# tie-il34-sdram.net
KiCad netlist of a schematic drawn in Altium Designer
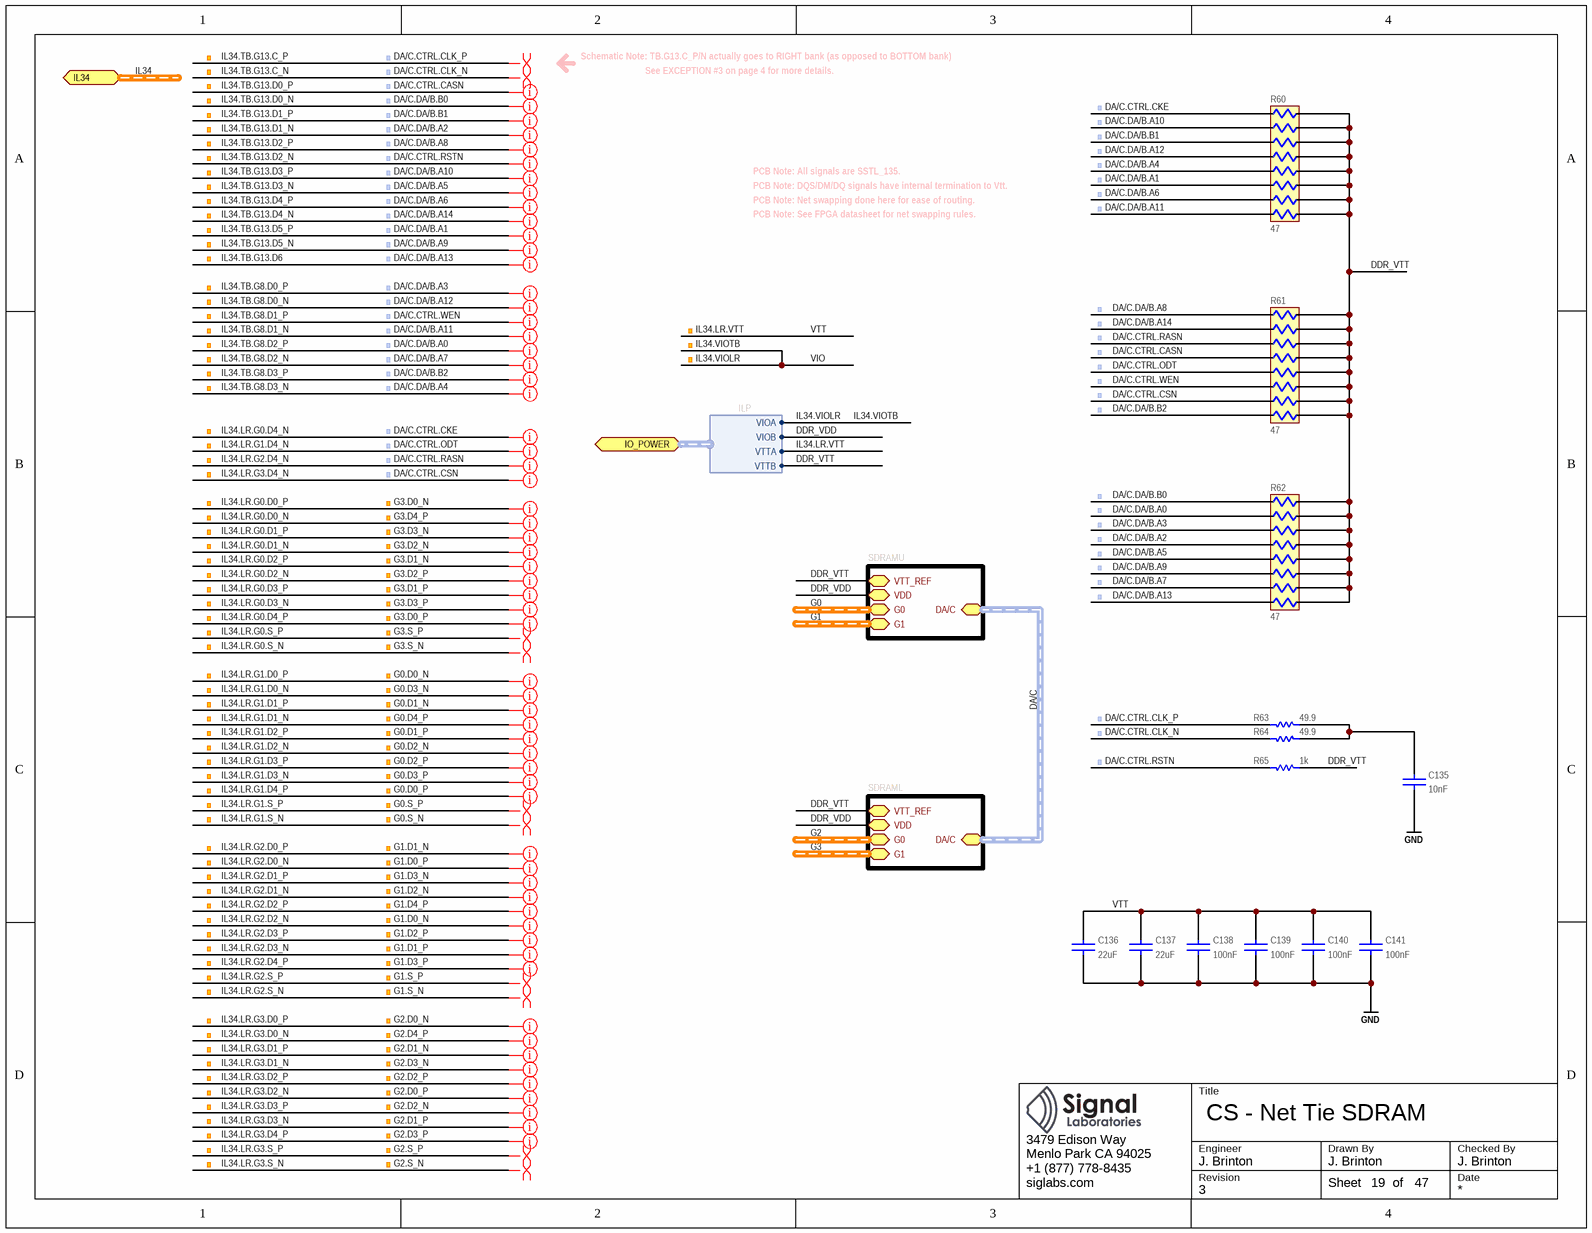
[diagram p0: tie-il34-sdram.SchDoc]

(export (version "E")
  (design (tool "Eeschema 10.0.6"))
  (components
    (comp (ref "C135")
      (value "10nF")
      (footprint "CAPC100X50X55L25N")
      (description "Ceramic Capacitor 10nF ±10% 50V X7R 0402")
      (fields (field (name "VOLTAGE") "50V") (field (name "MANUFACTURER") "Murata"))
      (libsource (lib "generic") (part "CAP"))
    )
    (comp (ref "C136")
      (value "22uF")
      (footprint "CAPC200X125X145L45N")
      (description "Ceramic Capacitor 22uF ±20% 10V X7S 0805")
      (fields (field (name "MANUFACTURER") "TDK") (field (name "TOLERANCE") "±20%"))
      (libsource (lib "generic") (part "CAP"))
    )
    (comp (ref "C137")
      (value "22uF")
      (footprint "CAPC200X125X145L45N")
      (description "Ceramic Capacitor 22uF ±20% 10V X7S 0805")
      (fields (field (name "MANUFACTURER") "TDK") (field (name "TOLERANCE") "±20%"))
      (libsource (lib "generic") (part "CAP"))
    )
    (comp (ref "C138")
      (value "100nF")
      (footprint "CAPC100X50X55L25N")
      (description "Ceramic Capacitor 100nF ±10% 50V X7R 0402")
      (fields (field (name "MANUFACTURER") "Murata") (field (name "TOLERANCE") "±10%"))
      (libsource (lib "generic") (part "CAP"))
    )
    (comp (ref "C139")
      (value "100nF")
      (footprint "CAPC100X50X55L25N")
      (description "Ceramic Capacitor 100nF ±10% 50V X7R 0402")
      (fields (field (name "MANUFACTURER") "Murata") (field (name "TOLERANCE") "±10%"))
      (libsource (lib "generic") (part "CAP"))
    )
    (comp (ref "C140")
      (value "100nF")
      (footprint "CAPC100X50X55L25N")
      (description "Ceramic Capacitor 100nF ±10% 50V X7R 0402")
      (fields (field (name "MANUFACTURER") "Murata") (field (name "TOLERANCE") "±10%"))
      (libsource (lib "generic") (part "CAP"))
    )
    (comp (ref "C141")
      (value "100nF")
      (footprint "CAPC100X50X55L25N")
      (description "Ceramic Capacitor 100nF ±10% 50V X7R 0402")
      (fields (field (name "MANUFACTURER") "Murata") (field (name "TOLERANCE") "±10%"))
      (libsource (lib "generic") (part "CAP"))
    )
    (comp (ref "R60")
      (value "47")
      (footprint "RESCAXE16P50_380X160X55L30X35N")
      (description "8 Resistor Array 47 ±5% 0.0625W 25V 1506")
      (fields (field (name "MANUFACTURER") "Panasonic") (field (name "TOLERANCE") "±5%"))
      (libsource (lib "altium-import") (part "root_0_EXB-2HV470JV_"))
    )
    (comp (ref "R61")
      (value "47")
      (footprint "RESCAXE16P50_380X160X55L30X35N")
      (description "8 Resistor Array 47 ±5% 0.0625W 25V 1506")
      (fields (field (name "MANUFACTURER") "Panasonic") (field (name "TOLERANCE") "±5%"))
      (libsource (lib "altium-import") (part "root_0_EXB-2HV470JV_"))
    )
    (comp (ref "R62")
      (value "47")
      (footprint "RESCAXE16P50_380X160X55L30X35N")
      (description "8 Resistor Array 47 ±5% 0.0625W 25V 1506")
      (fields (field (name "MANUFACTURER") "Panasonic") (field (name "TOLERANCE") "±5%"))
      (libsource (lib "altium-import") (part "root_0_EXB-2HV470JV_"))
    )
    (comp (ref "R63")
      (value "49.9")
      (footprint "RESC1005X40N")
      (description "Thick Film Resistor 49.9 ±1% 0.1W 50V 0402")
      (fields (field (name "TOLERANCE") "±1%") (field (name "MANUFACTURER") "Panasonic"))
      (libsource (lib "generic") (part "RES"))
    )
    (comp (ref "R64")
      (value "49.9")
      (footprint "RESC1005X40N")
      (description "Thick Film Resistor 49.9 ±1% 0.1W 50V 0402")
      (fields (field (name "TOLERANCE") "±1%") (field (name "MANUFACTURER") "Panasonic"))
      (libsource (lib "generic") (part "RES"))
    )
    (comp (ref "R65")
      (value "1k")
      (footprint "RESC1005X40N")
      (description "Thick Film Resistor 1k ±1% 0.1W 50V 0402")
      (fields (field (name "TOLERANCE") "±1%") (field (name "MANUFACTURER") "Panasonic"))
      (libsource (lib "generic") (part "RES"))
    )
  )
  (nets
    (net (code "8") (name "/DA{slash}C.CTRL.CASN") (class "Default")
      (node (ref "R61") (pin "4") (pinfunction "4_4") (pintype "passive"))
    )
    (net (code "9") (name "/DA{slash}C.CTRL.CKE") (class "Default")
      (node (ref "R60") (pin "1") (pintype "passive"))
    )
    (net (code "10") (name "/DA{slash}C.CTRL.CLK_N") (class "Default")
      (node (ref "R64") (pin "2") (pinfunction "2_2") (pintype "passive"))
    )
    (net (code "11") (name "/DA{slash}C.CTRL.CLK_P") (class "Default")
      (node (ref "R63") (pin "2") (pinfunction "2_2") (pintype "passive"))
    )
    (net (code "12") (name "/DA{slash}C.CTRL.CSN") (class "Default")
      (node (ref "R61") (pin "7") (pinfunction "7_7") (pintype "passive"))
    )
    (net (code "13") (name "/DA{slash}C.CTRL.ODT") (class "Default")
      (node (ref "R61") (pin "5") (pinfunction "5_5") (pintype "passive"))
    )
    (net (code "14") (name "/DA{slash}C.CTRL.RASN") (class "Default")
      (node (ref "R61") (pin "3") (pinfunction "3_3") (pintype "passive"))
    )
    (net (code "15") (name "/DA{slash}C.CTRL.RSTN") (class "Default")
      (node (ref "R65") (pin "1") (pinfunction "1_1") (pintype "passive"))
    )
    (net (code "16") (name "/DA{slash}C.CTRL.WEN") (class "Default")
      (node (ref "R61") (pin "6") (pinfunction "6_6") (pintype "passive"))
    )
    (net (code "17") (name "/DA{slash}C.DA{slash}B.A0") (class "Default")
      (node (ref "R62") (pin "2") (pinfunction "2_2") (pintype "passive"))
    )
    (net (code "18") (name "/DA{slash}C.DA{slash}B.A1") (class "Default")
      (node (ref "R60") (pin "6") (pinfunction "6_6") (pintype "passive"))
    )
    (net (code "19") (name "/DA{slash}C.DA{slash}B.A2") (class "Default")
      (node (ref "R62") (pin "4") (pinfunction "4_4") (pintype "passive"))
    )
    (net (code "20") (name "/DA{slash}C.DA{slash}B.A3") (class "Default")
      (node (ref "R62") (pin "3") (pinfunction "3_3") (pintype "passive"))
    )
    (net (code "21") (name "/DA{slash}C.DA{slash}B.A4") (class "Default")
      (node (ref "R60") (pin "5") (pinfunction "5_5") (pintype "passive"))
    )
    (net (code "22") (name "/DA{slash}C.DA{slash}B.A5") (class "Default")
      (node (ref "R62") (pin "5") (pinfunction "5_5") (pintype "passive"))
    )
    (net (code "23") (name "/DA{slash}C.DA{slash}B.A6") (class "Default")
      (node (ref "R60") (pin "7") (pinfunction "7_7") (pintype "passive"))
    )
    (net (code "24") (name "/DA{slash}C.DA{slash}B.A7") (class "Default")
      (node (ref "R62") (pin "7") (pinfunction "7_7") (pintype "passive"))
    )
    (net (code "25") (name "/DA{slash}C.DA{slash}B.A8") (class "Default")
      (node (ref "R61") (pin "1") (pintype "passive"))
    )
    (net (code "26") (name "/DA{slash}C.DA{slash}B.A9") (class "Default")
      (node (ref "R62") (pin "6") (pinfunction "6_6") (pintype "passive"))
    )
    (net (code "27") (name "/DA{slash}C.DA{slash}B.A10") (class "Default")
      (node (ref "R60") (pin "2") (pinfunction "2_2") (pintype "passive"))
    )
    (net (code "28") (name "/DA{slash}C.DA{slash}B.A11") (class "Default")
      (node (ref "R60") (pin "8") (pinfunction "8_8") (pintype "passive"))
    )
    (net (code "29") (name "/DA{slash}C.DA{slash}B.A12") (class "Default")
      (node (ref "R60") (pin "4") (pinfunction "4_4") (pintype "passive"))
    )
    (net (code "30") (name "/DA{slash}C.DA{slash}B.A13") (class "Default")
      (node (ref "R62") (pin "8") (pinfunction "8_8") (pintype "passive"))
    )
    (net (code "31") (name "/DA{slash}C.DA{slash}B.A14") (class "Default")
      (node (ref "R61") (pin "2") (pinfunction "2_2") (pintype "passive"))
    )
    (net (code "32") (name "/DA{slash}C.DA{slash}B.B0") (class "Default")
      (node (ref "R62") (pin "1") (pintype "passive"))
    )
    (net (code "33") (name "/DA{slash}C.DA{slash}B.B1") (class "Default")
      (node (ref "R60") (pin "3") (pinfunction "3_3") (pintype "passive"))
    )
    (net (code "34") (name "/DA{slash}C.DA{slash}B.B2") (class "Default")
      (node (ref "R61") (pin "8") (pinfunction "8_8") (pintype "passive"))
    )
    (net (code "36") (name "/DDR_VTT") (class "Default")
      (node (ref "R60") (pin "10") (pinfunction "10_10") (pintype "passive"))
      (node (ref "R60") (pin "11") (pinfunction "11_11") (pintype "passive"))
      (node (ref "R60") (pin "12") (pinfunction "12_12") (pintype "passive"))
      (node (ref "R60") (pin "13") (pinfunction "13_13") (pintype "passive"))
      (node (ref "R60") (pin "14") (pinfunction "14_14") (pintype "passive"))
      (node (ref "R60") (pin "15") (pinfunction "15_15") (pintype "passive"))
      (node (ref "R60") (pin "16") (pinfunction "16_16") (pintype "passive"))
      (node (ref "R60") (pin "9") (pinfunction "9_9") (pintype "passive"))
      (node (ref "R61") (pin "10") (pinfunction "10_10") (pintype "passive"))
      (node (ref "R61") (pin "11") (pinfunction "11_11") (pintype "passive"))
      (node (ref "R61") (pin "12") (pinfunction "12_12") (pintype "passive"))
      (node (ref "R61") (pin "13") (pinfunction "13_13") (pintype "passive"))
      (node (ref "R61") (pin "14") (pinfunction "14_14") (pintype "passive"))
      (node (ref "R61") (pin "15") (pinfunction "15_15") (pintype "passive"))
      (node (ref "R61") (pin "16") (pinfunction "16_16") (pintype "passive"))
      (node (ref "R61") (pin "9") (pinfunction "9_9") (pintype "passive"))
      (node (ref "R62") (pin "10") (pinfunction "10_10") (pintype "passive"))
      (node (ref "R62") (pin "11") (pinfunction "11_11") (pintype "passive"))
      (node (ref "R62") (pin "12") (pinfunction "12_12") (pintype "passive"))
      (node (ref "R62") (pin "13") (pinfunction "13_13") (pintype "passive"))
      (node (ref "R62") (pin "14") (pinfunction "14_14") (pintype "passive"))
      (node (ref "R62") (pin "15") (pinfunction "15_15") (pintype "passive"))
      (node (ref "R62") (pin "16") (pinfunction "16_16") (pintype "passive"))
      (node (ref "R62") (pin "9") (pinfunction "9_9") (pintype "passive"))
      (node (ref "R65") (pin "2") (pinfunction "2_2") (pintype "passive"))
    )
    (net (code "81") (name "/IL34.LR.VTT") (class "Default")
      (node (ref "C136") (pin "1") (pinfunction "1_1") (pintype "passive"))
      (node (ref "C137") (pin "1") (pinfunction "1_1") (pintype "passive"))
      (node (ref "C138") (pin "2") (pinfunction "2_2") (pintype "passive"))
      (node (ref "C139") (pin "2") (pinfunction "2_2") (pintype "passive"))
      (node (ref "C140") (pin "2") (pinfunction "2_2") (pintype "passive"))
      (node (ref "C141") (pin "2") (pinfunction "2_2") (pintype "passive"))
    )
    (net (code "90") (name "GND") (class "Default")
      (node (ref "C135") (pin "1") (pinfunction "1_1") (pintype "passive"))
      (node (ref "C136") (pin "2") (pinfunction "2_2") (pintype "passive"))
      (node (ref "C137") (pin "2") (pinfunction "2_2") (pintype "passive"))
      (node (ref "C138") (pin "1") (pinfunction "1_1") (pintype "passive"))
      (node (ref "C139") (pin "1") (pinfunction "1_1") (pintype "passive"))
      (node (ref "C140") (pin "1") (pinfunction "1_1") (pintype "passive"))
      (node (ref "C141") (pin "1") (pinfunction "1_1") (pintype "passive"))
    )
    (net (code "91") (name "Net-(C135-Pad2)") (class "Default")
      (node (ref "C135") (pin "2") (pinfunction "2_2") (pintype "passive"))
      (node (ref "R63") (pin "1") (pinfunction "1_1") (pintype "passive"))
      (node (ref "R64") (pin "1") (pinfunction "1_1") (pintype "passive"))
    )
  )
)
